# PCB2.net
KiCad netlist of a schematic drawn in Altium Designer
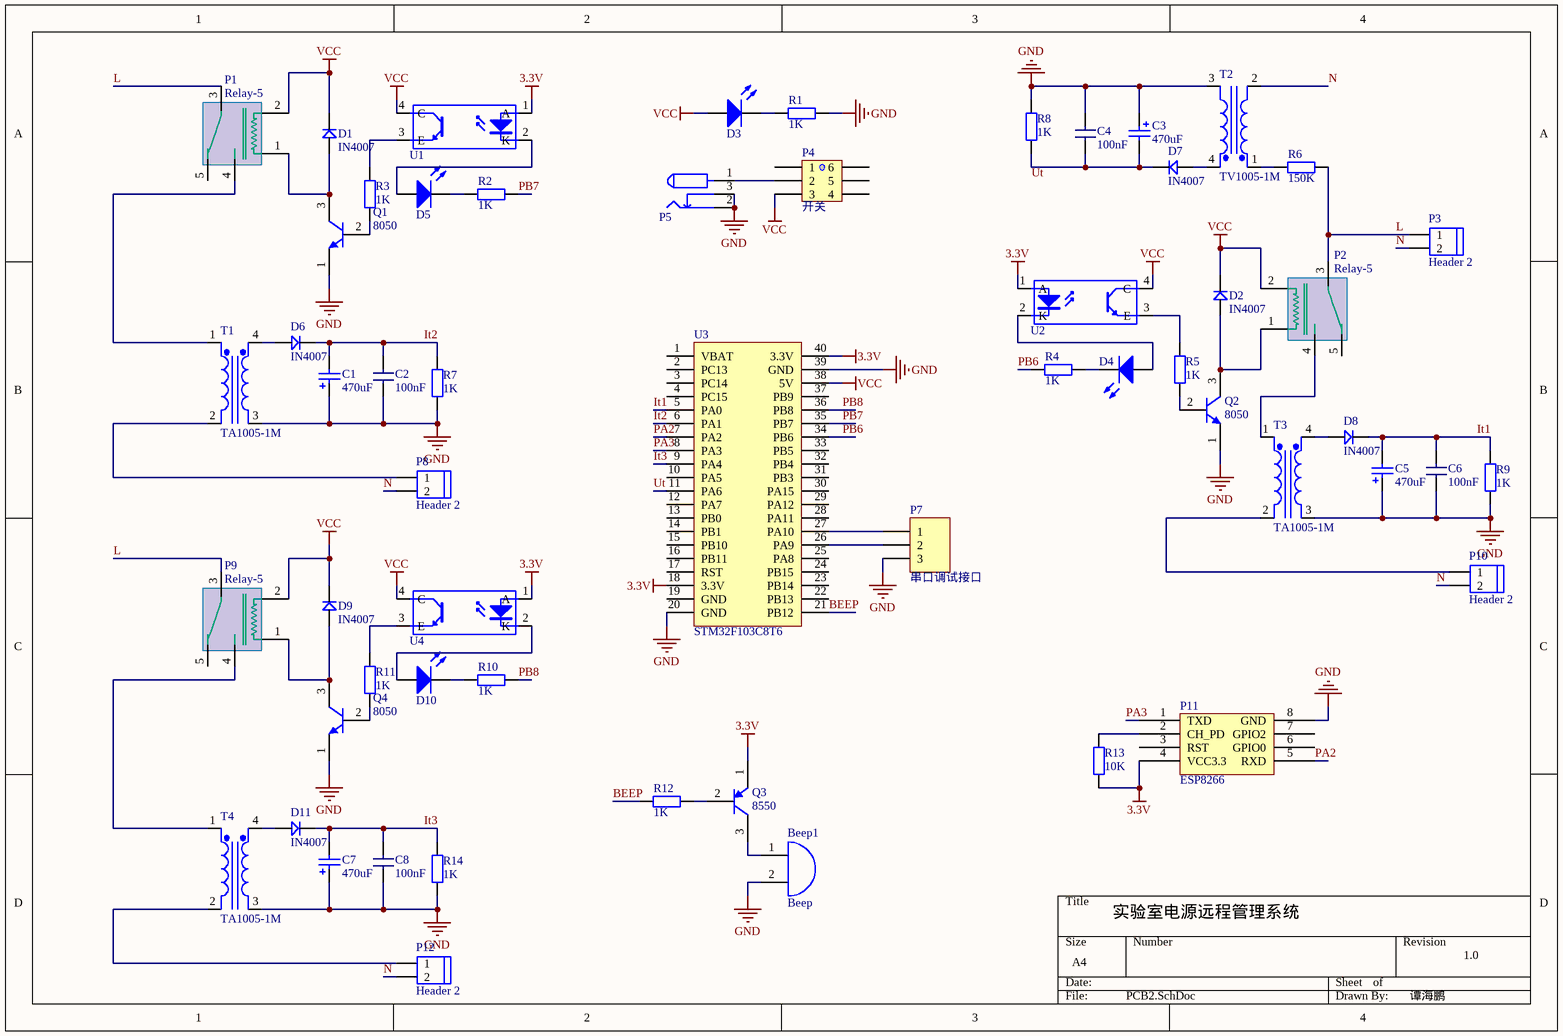
[diagram p0: PCB2.SchDoc]

(export (version "E")
  (design (tool "Eeschema 10.0.6"))
  (components
    (comp (ref "Beep1")
      (value "Beep")
      (footprint "Bell")
      (description "蜂鸣器")
      (libsource (lib "PCB2") (part "Bell"))
    )
    (comp (ref "C1")
      (value "470uF")
      (footprint "Cap")
      (description "电解电容")
      (fields (field (name "Comment") "CAP-A"))
      (libsource (lib "PCB2") (part "CAP-A"))
    )
    (comp (ref "C2")
      (value "100nF")
      (footprint "Cap")
      (description "瓷片电容")
      (fields (field (name "Comment") "CAP-B"))
      (libsource (lib "PCB2") (part "CAP-B"))
    )
    (comp (ref "C3")
      (value "470uF")
      (footprint "Cap")
      (description "电解电容")
      (fields (field (name "Comment") "CAP-A"))
      (libsource (lib "PCB2") (part "CAP-A"))
    )
    (comp (ref "C4")
      (value "100nF")
      (footprint "Cap")
      (description "瓷片电容")
      (fields (field (name "Comment") "CAP-B"))
      (libsource (lib "PCB2") (part "CAP-B"))
    )
    (comp (ref "C5")
      (value "470uF")
      (footprint "Cap")
      (description "电解电容")
      (fields (field (name "Comment") "CAP-A"))
      (libsource (lib "PCB2") (part "CAP-A"))
    )
    (comp (ref "C6")
      (value "100nF")
      (footprint "Cap")
      (description "瓷片电容")
      (fields (field (name "Comment") "CAP-B"))
      (libsource (lib "PCB2") (part "CAP-B"))
    )
    (comp (ref "C7")
      (value "470uF")
      (footprint "Cap")
      (description "电解电容")
      (fields (field (name "Comment") "CAP-A"))
      (libsource (lib "PCB2") (part "CAP-A"))
    )
    (comp (ref "C8")
      (value "100nF")
      (footprint "Cap")
      (description "瓷片电容")
      (fields (field (name "Comment") "CAP-B"))
      (libsource (lib "PCB2") (part "CAP-B"))
    )
    (comp (ref "D1")
      (value "IN4007")
      (footprint "Diode")
      (description "整流二极管")
      (fields (field (name "Comment") "Diode"))
      (libsource (lib "PCB2") (part "Diode"))
    )
    (comp (ref "D2")
      (value "IN4007")
      (footprint "Diode")
      (description "整流二极管")
      (fields (field (name "Comment") "Diode"))
      (libsource (lib "PCB2") (part "Diode"))
    )
    (comp (ref "D3") (value "LED") (footprint "LED") (libsource (lib "Component") (part "LED")))
    (comp (ref "D4") (value "LED") (footprint "LED") (libsource (lib "Component") (part "LED")))
    (comp (ref "D5") (value "LED") (footprint "LED") (libsource (lib "Component") (part "LED")))
    (comp (ref "D6")
      (value "IN4007")
      (footprint "Diode")
      (description "整流二极管")
      (fields (field (name "Comment") "Diode"))
      (libsource (lib "PCB2") (part "Diode"))
    )
    (comp (ref "D7")
      (value "IN4007")
      (footprint "Diode")
      (description "整流二极管")
      (fields (field (name "Comment") "Diode"))
      (libsource (lib "PCB2") (part "Diode"))
    )
    (comp (ref "D8")
      (value "IN4007")
      (footprint "Diode")
      (description "整流二极管")
      (fields (field (name "Comment") "Diode"))
      (libsource (lib "PCB2") (part "Diode"))
    )
    (comp (ref "D9")
      (value "IN4007")
      (footprint "Diode")
      (description "整流二极管")
      (fields (field (name "Comment") "Diode"))
      (libsource (lib "PCB2") (part "Diode"))
    )
    (comp (ref "D10") (value "LED") (footprint "LED") (libsource (lib "Component") (part "LED")))
    (comp (ref "D11")
      (value "IN4007")
      (footprint "Diode")
      (description "整流二极管")
      (fields (field (name "Comment") "Diode"))
      (libsource (lib "PCB2") (part "Diode"))
    )
    (comp (ref "P1")
      (value "Relay-5")
      (footprint "Relay")
      (description "5针继电器")
      (libsource (lib "") (part "Relay-5_1"))
    )
    (comp (ref "P2")
      (value "Relay-5")
      (footprint "Relay")
      (description "5针继电器")
      (libsource (lib "原理图库") (part "Relay-5"))
    )
    (comp (ref "P3")
      (value "Header 2")
      (footprint "HDR1X2")
      (description "两孔端子")
      (libsource (lib "原理图库") (part "Header 2"))
    )
    (comp (ref "P4") (value "开关") (footprint "Switch") (libsource (lib "PCB2") (part "Switch")))
    (comp (ref "P5")
      (value "电源插座")
      (footprint "DC")
      (description "DC电源插口")
      (libsource (lib "PCB2") (part "POWER"))
    )
    (comp (ref "P7")
      (value "串口调试接口")
      (footprint "HDR1X3")
      (description "Header, 3-Pin")
      (fields (field (name "PUBLISHER") "Altium Limited"))
      (libsource (lib "Miscellaneous Connectors") (part "Header 3"))
    )
    (comp (ref "P8")
      (value "Header 2")
      (footprint "HDR1X2")
      (description "两孔端子")
      (libsource (lib "原理图库") (part "Header 2"))
    )
    (comp (ref "P9")
      (value "Relay-5")
      (footprint "Relay")
      (description "5针继电器")
      (libsource (lib "") (part "Relay-5_1"))
    )
    (comp (ref "P10")
      (value "Header 2")
      (footprint "HDR1X2")
      (description "两孔端子")
      (libsource (lib "原理图库") (part "Header 2"))
    )
    (comp (ref "P11")
      (value "ESP8266")
      (footprint "ESP8266")
      (description "WIFI模块（8针）")
      (libsource (lib "PCB2") (part "ESP8266"))
    )
    (comp (ref "P12")
      (value "Header 2")
      (footprint "HDR1X2")
      (description "两孔端子")
      (libsource (lib "原理图库") (part "Header 2"))
    )
    (comp (ref "Q1")
      (value "8050")
      (footprint "Triode")
      (description "NPN")
      (libsource (lib "原理图库") (part "NPN"))
    )
    (comp (ref "Q2")
      (value "8050")
      (footprint "Triode")
      (description "NPN")
      (libsource (lib "原理图库") (part "NPN"))
    )
    (comp (ref "Q3")
      (value "8550")
      (footprint "Triode")
      (description "PNP")
      (libsource (lib "原理图库") (part "PNP"))
    )
    (comp (ref "Q4")
      (value "8050")
      (footprint "Triode")
      (description "NPN")
      (libsource (lib "原理图库") (part "NPN"))
    )
    (comp (ref "R1")
      (value "1K")
      (footprint "RES")
      (description "电阻")
      (fields (field (name "Comment") "RES"))
      (libsource (lib "") (part "RES_1"))
    )
    (comp (ref "R2")
      (value "1K")
      (footprint "RES")
      (description "电阻")
      (fields (field (name "Comment") "RES"))
      (libsource (lib "") (part "RES_1"))
    )
    (comp (ref "R3")
      (value "1K")
      (footprint "RES")
      (description "电阻")
      (fields (field (name "Comment") "RES"))
      (libsource (lib "PCB2") (part "RES"))
    )
    (comp (ref "R4")
      (value "1K")
      (footprint "RES")
      (description "电阻")
      (fields (field (name "Comment") "RES"))
      (libsource (lib "") (part "RES_1"))
    )
    (comp (ref "R5")
      (value "1K")
      (footprint "RES")
      (description "电阻")
      (fields (field (name "Comment") "RES"))
      (libsource (lib "") (part "RES_2"))
    )
    (comp (ref "R6")
      (value "150K")
      (footprint "RES")
      (description "电阻")
      (fields (field (name "Comment") "RES"))
      (libsource (lib "") (part "RES_1"))
    )
    (comp (ref "R7")
      (value "1K")
      (footprint "RES")
      (description "电阻")
      (fields (field (name "Comment") "RES"))
      (libsource (lib "PCB2") (part "RES"))
    )
    (comp (ref "R8")
      (value "1K")
      (footprint "RES")
      (description "电阻")
      (fields (field (name "Comment") "RES"))
      (libsource (lib "") (part "RES_2"))
    )
    (comp (ref "R9")
      (value "1K")
      (footprint "RES")
      (description "电阻")
      (fields (field (name "Comment") "RES"))
      (libsource (lib "PCB2") (part "RES"))
    )
    (comp (ref "R10")
      (value "1K")
      (footprint "RES")
      (description "电阻")
      (fields (field (name "Comment") "RES"))
      (libsource (lib "") (part "RES_3"))
    )
    (comp (ref "R11")
      (value "1K")
      (footprint "RES")
      (description "电阻")
      (fields (field (name "Comment") "RES"))
      (libsource (lib "PCB2") (part "RES"))
    )
    (comp (ref "R12")
      (value "1K")
      (footprint "RES")
      (description "电阻")
      (fields (field (name "Comment") "RES"))
      (libsource (lib "") (part "RES_3"))
    )
    (comp (ref "R13")
      (value "10K")
      (footprint "RES")
      (description "电阻")
      (fields (field (name "Comment") "RES"))
      (libsource (lib "PCB2") (part "RES"))
    )
    (comp (ref "R14")
      (value "1K")
      (footprint "RES")
      (description "电阻")
      (fields (field (name "Comment") "RES"))
      (libsource (lib "PCB2") (part "RES"))
    )
    (comp (ref "T1")
      (value "TA1005-1M")
      (footprint "Transforme")
      (description "电流互感器")
      (libsource (lib "PCB2") (part "Transforme-A"))
    )
    (comp (ref "T2")
      (value "TV1005-1M")
      (footprint "Transforme")
      (description "电压互感器")
      (libsource (lib "PCB2") (part "Transforme-V"))
    )
    (comp (ref "T3")
      (value "TA1005-1M")
      (footprint "Transforme")
      (description "电流互感器")
      (libsource (lib "PCB2") (part "Transforme-A"))
    )
    (comp (ref "T4")
      (value "TA1005-1M")
      (footprint "Transforme")
      (description "电流互感器")
      (libsource (lib "PCB2") (part "Transforme-A"))
    )
    (comp (ref "U1")
      (value "Optoisolator")
      (footprint "DIP-4")
      (description "光耦隔离器")
      (libsource (lib "PCB2") (part "Optoisolator"))
    )
    (comp (ref "U2")
      (value "Optoisolator")
      (footprint "DIP-4")
      (description "光耦隔离器")
      (libsource (lib "PCB2") (part "Optoisolator"))
    )
    (comp (ref "U3")
      (value "STM32F103C8T6")
      (footprint "STM32F103C8T6")
      (description "STM32最小系统（40针）")
      (libsource (lib "PCB2") (part "STM32F103C8T6"))
    )
    (comp (ref "U4")
      (value "Optoisolator")
      (footprint "DIP-4")
      (description "光耦隔离器")
      (libsource (lib "PCB2") (part "Optoisolator"))
    )
  )
  (nets
    (net (code "1") (name "/BEEP") (class "Default")
      (node (ref "R12") (pin "1") (pinfunction "1_1") (pintype "passive"))
      (node (ref "U3") (pin "21") (pinfunction "PB12_21") (pintype "passive"))
    )
    (net (code "2") (name "/It1") (class "Default")
      (node (ref "C5") (pin "2") (pinfunction "2_2") (pintype "passive"))
      (node (ref "C6") (pin "2") (pintype "passive"))
      (node (ref "D8") (pin "2") (pintype "passive"))
      (node (ref "R9") (pin "2") (pinfunction "2_2") (pintype "passive"))
      (node (ref "U3") (pin "5") (pinfunction "PA0_5") (pintype "passive"))
    )
    (net (code "3") (name "/It2") (class "Default")
      (node (ref "C1") (pin "2") (pinfunction "2_2") (pintype "passive"))
      (node (ref "C2") (pin "2") (pintype "passive"))
      (node (ref "D6") (pin "2") (pintype "passive"))
      (node (ref "R7") (pin "2") (pinfunction "2_2") (pintype "passive"))
      (node (ref "U3") (pin "6") (pinfunction "PA1_6") (pintype "passive"))
    )
    (net (code "4") (name "/It3") (class "Default")
      (node (ref "C7") (pin "2") (pinfunction "2_2") (pintype "passive"))
      (node (ref "C8") (pin "2") (pintype "passive"))
      (node (ref "D11") (pin "2") (pintype "passive"))
      (node (ref "R14") (pin "2") (pinfunction "2_2") (pintype "passive"))
      (node (ref "U3") (pin "9") (pinfunction "PA4_9") (pintype "passive"))
    )
    (net (code "5") (name "/L") (class "Default")
      (node (ref "P1") (pin "3") (pinfunction "3_3") (pintype "passive"))
      (node (ref "P2") (pin "3") (pinfunction "3_3") (pintype "passive"))
      (node (ref "P3") (pin "1") (pinfunction "1_1") (pintype "passive"))
      (node (ref "P9") (pin "3") (pinfunction "3_3") (pintype "passive"))
      (node (ref "R6") (pin "1") (pinfunction "1_1") (pintype "passive"))
    )
    (net (code "6") (name "/N") (class "Default")
      (node (ref "P10") (pin "2") (pinfunction "2_2") (pintype "passive"))
      (node (ref "P12") (pin "2") (pinfunction "2_2") (pintype "passive"))
      (node (ref "P3") (pin "2") (pinfunction "2_2") (pintype "passive"))
      (node (ref "P8") (pin "2") (pinfunction "2_2") (pintype "passive"))
      (node (ref "T2") (pin "2") (pinfunction "Pri-_2") (pintype "passive"))
    )
    (net (code "7") (name "/PA2") (class "Default")
      (node (ref "P11") (pin "5") (pinfunction "RXD_5") (pintype "passive"))
      (node (ref "U3") (pin "7") (pinfunction "PA2_7") (pintype "passive"))
    )
    (net (code "8") (name "/PA3") (class "Default")
      (node (ref "P11") (pin "1") (pinfunction "TXD_1") (pintype "passive"))
      (node (ref "U3") (pin "8") (pinfunction "PA3_8") (pintype "passive"))
    )
    (net (code "9") (name "/PB6") (class "Default")
      (node (ref "R4") (pin "2") (pinfunction "2_2") (pintype "passive"))
      (node (ref "U3") (pin "34") (pinfunction "PB6_34") (pintype "passive"))
    )
    (net (code "10") (name "/PB7") (class "Default")
      (node (ref "R2") (pin "1") (pinfunction "1_1") (pintype "passive"))
      (node (ref "U3") (pin "35") (pinfunction "PB7_35") (pintype "passive"))
    )
    (net (code "11") (name "/PB8") (class "Default")
      (node (ref "R10") (pin "2") (pinfunction "2_2") (pintype "passive"))
      (node (ref "U3") (pin "36") (pinfunction "PB8_36") (pintype "passive"))
    )
    (net (code "12") (name "/Ut") (class "Default")
      (node (ref "U3") (pin "11") (pinfunction "PA6_11") (pintype "passive"))
    )
    (net (code "13") (name "3.3V") (class "Default")
      (node (ref "P11") (pin "4") (pinfunction "VCC3.3_4") (pintype "passive"))
      (node (ref "Q3") (pin "1") (pinfunction "E_1") (pintype "passive"))
      (node (ref "R13") (pin "1") (pinfunction "1_1") (pintype "passive"))
      (node (ref "U1") (pin "1") (pinfunction "A_1") (pintype "passive"))
      (node (ref "U2") (pin "1") (pinfunction "A_1") (pintype "passive"))
      (node (ref "U3") (pin "18") (pinfunction "3.3V_18") (pintype "passive"))
      (node (ref "U3") (pin "40") (pinfunction "3.3V_40") (pintype "passive"))
      (node (ref "U4") (pin "1") (pinfunction "A_1") (pintype "passive"))
    )
    (net (code "14") (name "GND") (class "Default")
      (node (ref "Beep1") (pin "2") (pinfunction "B_2") (pintype "passive"))
      (node (ref "C1") (pin "1") (pinfunction "1_1") (pintype "passive"))
      (node (ref "C2") (pin "1") (pintype "passive"))
      (node (ref "C3") (pin "1") (pinfunction "1_1") (pintype "passive"))
      (node (ref "C4") (pin "1") (pintype "passive"))
      (node (ref "C5") (pin "1") (pinfunction "1_1") (pintype "passive"))
      (node (ref "C6") (pin "1") (pintype "passive"))
      (node (ref "C7") (pin "1") (pinfunction "1_1") (pintype "passive"))
      (node (ref "C8") (pin "1") (pintype "passive"))
      (node (ref "P11") (pin "8") (pinfunction "GND_8") (pintype "passive"))
      (node (ref "P5") (pin "2") (pintype "passive"))
      (node (ref "P5") (pin "3") (pintype "passive"))
      (node (ref "P7") (pin "3") (pinfunction "3_3") (pintype "passive"))
      (node (ref "Q1") (pin "1") (pinfunction "2_1") (pintype "passive"))
      (node (ref "Q2") (pin "1") (pinfunction "2_1") (pintype "passive"))
      (node (ref "Q4") (pin "1") (pinfunction "2_1") (pintype "passive"))
      (node (ref "R1") (pin "1") (pinfunction "1_1") (pintype "passive"))
      (node (ref "R14") (pin "1") (pinfunction "1_1") (pintype "passive"))
      (node (ref "R7") (pin "1") (pinfunction "1_1") (pintype "passive"))
      (node (ref "R8") (pin "1") (pinfunction "1_1") (pintype "passive"))
      (node (ref "R9") (pin "1") (pinfunction "1_1") (pintype "passive"))
      (node (ref "T1") (pin "3") (pinfunction "Sec-_3") (pintype "passive"))
      (node (ref "T2") (pin "3") (pinfunction "Sec-_3") (pintype "passive"))
      (node (ref "T3") (pin "3") (pinfunction "Sec-_3") (pintype "passive"))
      (node (ref "T4") (pin "3") (pinfunction "Sec-_3") (pintype "passive"))
      (node (ref "U3") (pin "20") (pinfunction "GND_20") (pintype "passive"))
      (node (ref "U3") (pin "39") (pinfunction "GND_39") (pintype "passive"))
    )
    (net (code "15") (name "Net-(Beep1-A)") (class "Default")
      (node (ref "Beep1") (pin "1") (pinfunction "A_1") (pintype "passive"))
      (node (ref "Q3") (pin "3") (pinfunction "C_3") (pintype "passive"))
    )
    (net (code "16") (name "Net-(C3-Pad2)") (class "Default")
      (node (ref "C3") (pin "2") (pinfunction "2_2") (pintype "passive"))
      (node (ref "C4") (pin "2") (pintype "passive"))
      (node (ref "D7") (pin "2") (pintype "passive"))
      (node (ref "R8") (pin "2") (pinfunction "2_2") (pintype "passive"))
    )
    (net (code "17") (name "Net-(D3-K)") (class "Default")
      (node (ref "D3") (pin "2") (pinfunction "K_2") (pintype "passive"))
      (node (ref "R1") (pin "2") (pinfunction "2_2") (pintype "passive"))
    )
    (net (code "18") (name "Net-(D4-A)") (class "Default")
      (node (ref "D4") (pin "1") (pinfunction "A_1") (pintype "passive"))
      (node (ref "U2") (pin "2") (pinfunction "K_2") (pintype "passive"))
    )
    (net (code "19") (name "Net-(D4-K)") (class "Default")
      (node (ref "D4") (pin "2") (pinfunction "K_2") (pintype "passive"))
      (node (ref "R4") (pin "1") (pinfunction "1_1") (pintype "passive"))
    )
    (net (code "20") (name "Net-(D5-A)") (class "Default")
      (node (ref "D5") (pin "1") (pinfunction "A_1") (pintype "passive"))
      (node (ref "U1") (pin "2") (pinfunction "K_2") (pintype "passive"))
    )
    (net (code "21") (name "Net-(D5-K)") (class "Default")
      (node (ref "D5") (pin "2") (pinfunction "K_2") (pintype "passive"))
      (node (ref "R2") (pin "2") (pinfunction "2_2") (pintype "passive"))
    )
    (net (code "22") (name "Net-(D10-A)") (class "Default")
      (node (ref "D10") (pin "1") (pinfunction "A_1") (pintype "passive"))
      (node (ref "U4") (pin "2") (pinfunction "K_2") (pintype "passive"))
    )
    (net (code "23") (name "Net-(D10-K)") (class "Default")
      (node (ref "D10") (pin "2") (pinfunction "K_2") (pintype "passive"))
      (node (ref "R10") (pin "1") (pinfunction "1_1") (pintype "passive"))
    )
    (net (code "24") (name "Net-(P4-Pad2)") (class "Default")
      (node (ref "P4") (pin "2") (pinfunction "2_2") (pintype "passive"))
      (node (ref "P5") (pin "1") (pintype "passive"))
    )
    (net (code "25") (name "Net-(P11-CH_PD)") (class "Default")
      (node (ref "P11") (pin "2") (pinfunction "CH_PD_2") (pintype "passive"))
      (node (ref "R13") (pin "2") (pinfunction "2_2") (pintype "passive"))
    )
    (net (code "26") (name "Net-(Q1-B)") (class "Default")
      (node (ref "Q1") (pin "2") (pinfunction "B_2") (pintype "passive"))
      (node (ref "R3") (pin "1") (pinfunction "1_1") (pintype "passive"))
    )
    (net (code "27") (name "Net-(Q1-C)") (class "Default")
      (node (ref "D1") (pin "1") (pintype "passive"))
      (node (ref "P1") (pin "1") (pinfunction "1_1") (pintype "passive"))
      (node (ref "Q1") (pin "3") (pinfunction "C_3") (pintype "passive"))
    )
    (net (code "28") (name "Net-(Q2-B)") (class "Default")
      (node (ref "Q2") (pin "2") (pinfunction "B_2") (pintype "passive"))
      (node (ref "R5") (pin "2") (pinfunction "2_2") (pintype "passive"))
    )
    (net (code "29") (name "Net-(Q2-C)") (class "Default")
      (node (ref "D2") (pin "1") (pintype "passive"))
      (node (ref "P2") (pin "1") (pinfunction "1_1") (pintype "passive"))
      (node (ref "Q2") (pin "3") (pinfunction "C_3") (pintype "passive"))
    )
    (net (code "30") (name "Net-(Q3-B)") (class "Default")
      (node (ref "Q3") (pin "2") (pinfunction "B_2") (pintype "passive"))
      (node (ref "R12") (pin "2") (pinfunction "2_2") (pintype "passive"))
    )
    (net (code "31") (name "Net-(Q4-B)") (class "Default")
      (node (ref "Q4") (pin "2") (pinfunction "B_2") (pintype "passive"))
      (node (ref "R11") (pin "1") (pinfunction "1_1") (pintype "passive"))
    )
    (net (code "32") (name "Net-(Q4-C)") (class "Default")
      (node (ref "D9") (pin "1") (pintype "passive"))
      (node (ref "P9") (pin "1") (pinfunction "1_1") (pintype "passive"))
      (node (ref "Q4") (pin "3") (pinfunction "C_3") (pintype "passive"))
    )
    (net (code "33") (name "Net-(T1-Pri+)") (class "Default")
      (node (ref "P1") (pin "4") (pinfunction "4_4") (pintype "passive"))
      (node (ref "T1") (pin "1") (pinfunction "Pri+_1") (pintype "passive"))
    )
    (net (code "34") (name "Net-(T1-Pri-)") (class "Default")
      (node (ref "P8") (pin "1") (pinfunction "1_1") (pintype "passive"))
      (node (ref "T1") (pin "2") (pinfunction "Pri-_2") (pintype "passive"))
    )
    (net (code "35") (name "Net-(T1-Sec+)") (class "Default")
      (node (ref "D6") (pin "1") (pintype "passive"))
      (node (ref "T1") (pin "4") (pinfunction "Sec+_4") (pintype "passive"))
    )
    (net (code "36") (name "Net-(T2-Pri+)") (class "Default")
      (node (ref "R6") (pin "2") (pinfunction "2_2") (pintype "passive"))
      (node (ref "T2") (pin "1") (pinfunction "Pri+_1") (pintype "passive"))
    )
    (net (code "37") (name "Net-(T2-Sec+)") (class "Default")
      (node (ref "D7") (pin "1") (pintype "passive"))
      (node (ref "T2") (pin "4") (pinfunction "Sec+_4") (pintype "passive"))
    )
    (net (code "38") (name "Net-(T3-Pri+)") (class "Default")
      (node (ref "P2") (pin "4") (pinfunction "4_4") (pintype "passive"))
      (node (ref "T3") (pin "1") (pinfunction "Pri+_1") (pintype "passive"))
    )
    (net (code "39") (name "Net-(T3-Pri-)") (class "Default")
      (node (ref "P10") (pin "1") (pinfunction "1_1") (pintype "passive"))
      (node (ref "T3") (pin "2") (pinfunction "Pri-_2") (pintype "passive"))
    )
    (net (code "40") (name "Net-(T3-Sec+)") (class "Default")
      (node (ref "D8") (pin "1") (pintype "passive"))
      (node (ref "T3") (pin "4") (pinfunction "Sec+_4") (pintype "passive"))
    )
    (net (code "41") (name "Net-(T4-Pri+)") (class "Default")
      (node (ref "P9") (pin "4") (pinfunction "4_4") (pintype "passive"))
      (node (ref "T4") (pin "1") (pinfunction "Pri+_1") (pintype "passive"))
    )
    (net (code "42") (name "Net-(T4-Pri-)") (class "Default")
      (node (ref "P12") (pin "1") (pinfunction "1_1") (pintype "passive"))
      (node (ref "T4") (pin "2") (pinfunction "Pri-_2") (pintype "passive"))
    )
    (net (code "43") (name "Net-(T4-Sec+)") (class "Default")
      (node (ref "D11") (pin "1") (pintype "passive"))
      (node (ref "T4") (pin "4") (pinfunction "Sec+_4") (pintype "passive"))
    )
    (net (code "44") (name "Net-(U1-E)") (class "Default")
      (node (ref "R3") (pin "2") (pinfunction "2_2") (pintype "passive"))
      (node (ref "U1") (pin "3") (pinfunction "E_3") (pintype "passive"))
    )
    (net (code "45") (name "Net-(U2-E)") (class "Default")
      (node (ref "R5") (pin "1") (pinfunction "1_1") (pintype "passive"))
      (node (ref "U2") (pin "3") (pinfunction "E_3") (pintype "passive"))
    )
    (net (code "46") (name "Net-(U3-PA9)") (class "Default")
      (node (ref "P7") (pin "2") (pinfunction "2_2") (pintype "passive"))
      (node (ref "U3") (pin "26") (pinfunction "PA9_26") (pintype "passive"))
    )
    (net (code "47") (name "Net-(U3-PA10)") (class "Default")
      (node (ref "P7") (pin "1") (pinfunction "1_1") (pintype "passive"))
      (node (ref "U3") (pin "27") (pinfunction "PA10_27") (pintype "passive"))
    )
    (net (code "48") (name "Net-(U4-E)") (class "Default")
      (node (ref "R11") (pin "2") (pinfunction "2_2") (pintype "passive"))
      (node (ref "U4") (pin "3") (pinfunction "E_3") (pintype "passive"))
    )
    (net (code "49") (name "VCC") (class "Default")
      (node (ref "D1") (pin "2") (pintype "passive"))
      (node (ref "D2") (pin "2") (pintype "passive"))
      (node (ref "D3") (pin "1") (pinfunction "A_1") (pintype "passive"))
      (node (ref "D9") (pin "2") (pintype "passive"))
      (node (ref "P1") (pin "2") (pinfunction "2_2") (pintype "passive"))
      (node (ref "P2") (pin "2") (pinfunction "2_2") (pintype "passive"))
      (node (ref "P4") (pin "3") (pinfunction "3_3") (pintype "passive"))
      (node (ref "P9") (pin "2") (pinfunction "2_2") (pintype "passive"))
      (node (ref "U1") (pin "4") (pinfunction "C_4") (pintype "passive"))
      (node (ref "U2") (pin "4") (pinfunction "C_4") (pintype "passive"))
      (node (ref "U3") (pin "38") (pinfunction "5V_38") (pintype "passive"))
      (node (ref "U4") (pin "4") (pinfunction "C_4") (pintype "passive"))
    )
    (net (code "50") (name "unconnected-(P1-Pad5)") (class "Default")
      (node (ref "P1") (pin "5") (pinfunction "5_5") (pintype "passive"))
    )
    (net (code "51") (name "unconnected-(P2-Pad5)") (class "Default")
      (node (ref "P2") (pin "5") (pinfunction "5_5") (pintype "passive"))
    )
    (net (code "52") (name "unconnected-(P4-Pad1)") (class "Default")
      (node (ref "P4") (pin "1") (pinfunction "1_1") (pintype "passive"))
    )
    (net (code "53") (name "unconnected-(P4-Pad4)") (class "Default")
      (node (ref "P4") (pin "4") (pinfunction "4_4") (pintype "passive"))
    )
    (net (code "54") (name "unconnected-(P4-Pad5)") (class "Default")
      (node (ref "P4") (pin "5") (pinfunction "5_5") (pintype "passive"))
    )
    (net (code "55") (name "unconnected-(P4-Pad6)") (class "Default")
      (node (ref "P4") (pin "6") (pinfunction "6_6") (pintype "passive"))
    )
    (net (code "56") (name "unconnected-(P9-Pad5)") (class "Default")
      (node (ref "P9") (pin "5") (pinfunction "5_5") (pintype "passive"))
    )
    (net (code "57") (name "unconnected-(P11-GPIO0-Pad6)") (class "Default")
      (node (ref "P11") (pin "6") (pinfunction "GPIO0_6") (pintype "passive"))
    )
    (net (code "58") (name "unconnected-(P11-GPIO2-Pad7)") (class "Default")
      (node (ref "P11") (pin "7") (pinfunction "GPIO2_7") (pintype "passive"))
    )
    (net (code "59") (name "unconnected-(P11-RST-Pad3)") (class "Default")
      (node (ref "P11") (pin "3") (pinfunction "RST_3") (pintype "passive"))
    )
    (net (code "60") (name "unconnected-(U3-GND-Pad19)") (class "Default")
      (node (ref "U3") (pin "19") (pinfunction "GND_19") (pintype "passive"))
    )
    (net (code "61") (name "unconnected-(U3-PA5-Pad10)") (class "Default")
      (node (ref "U3") (pin "10") (pinfunction "PA5_10") (pintype "passive"))
    )
    (net (code "62") (name "unconnected-(U3-PA7-Pad12)") (class "Default")
      (node (ref "U3") (pin "12") (pinfunction "PA7_12") (pintype "passive"))
    )
    (net (code "63") (name "unconnected-(U3-PA8-Pad25)") (class "Default")
      (node (ref "U3") (pin "25") (pinfunction "PA8_25") (pintype "passive"))
    )
    (net (code "64") (name "unconnected-(U3-PA11-Pad28)") (class "Default")
      (node (ref "U3") (pin "28") (pinfunction "PA11_28") (pintype "passive"))
    )
    (net (code "65") (name "unconnected-(U3-PA12-Pad29)") (class "Default")
      (node (ref "U3") (pin "29") (pinfunction "PA12_29") (pintype "passive"))
    )
    (net (code "66") (name "unconnected-(U3-PA15-Pad30)") (class "Default")
      (node (ref "U3") (pin "30") (pinfunction "PA15_30") (pintype "passive"))
    )
    (net (code "67") (name "unconnected-(U3-PB0-Pad13)") (class "Default")
      (node (ref "U3") (pin "13") (pinfunction "PB0_13") (pintype "passive"))
    )
    (net (code "68") (name "unconnected-(U3-PB1-Pad14)") (class "Default")
      (node (ref "U3") (pin "14") (pinfunction "PB1_14") (pintype "passive"))
    )
    (net (code "69") (name "unconnected-(U3-PB3-Pad31)") (class "Default")
      (node (ref "U3") (pin "31") (pinfunction "PB3_31") (pintype "passive"))
    )
    (net (code "70") (name "unconnected-(U3-PB4-Pad32)") (class "Default")
      (node (ref "U3") (pin "32") (pinfunction "PB4_32") (pintype "passive"))
    )
    (net (code "71") (name "unconnected-(U3-PB5-Pad33)") (class "Default")
      (node (ref "U3") (pin "33") (pinfunction "PB5_33") (pintype "passive"))
    )
    (net (code "72") (name "unconnected-(U3-PB9-Pad37)") (class "Default")
      (node (ref "U3") (pin "37") (pinfunction "PB9_37") (pintype "passive"))
    )
    (net (code "73") (name "unconnected-(U3-PB10-Pad15)") (class "Default")
      (node (ref "U3") (pin "15") (pinfunction "PB10_15") (pintype "passive"))
    )
    (net (code "74") (name "unconnected-(U3-PB11-Pad16)") (class "Default")
      (node (ref "U3") (pin "16") (pinfunction "PB11_16") (pintype "passive"))
    )
    (net (code "75") (name "unconnected-(U3-PB13-Pad22)") (class "Default")
      (node (ref "U3") (pin "22") (pinfunction "PB13_22") (pintype "passive"))
    )
    (net (code "76") (name "unconnected-(U3-PB14-Pad23)") (class "Default")
      (node (ref "U3") (pin "23") (pinfunction "PB14_23") (pintype "passive"))
    )
    (net (code "77") (name "unconnected-(U3-PB15-Pad24)") (class "Default")
      (node (ref "U3") (pin "24") (pinfunction "PB15_24") (pintype "passive"))
    )
    (net (code "78") (name "unconnected-(U3-PC13-Pad2)") (class "Default")
      (node (ref "U3") (pin "2") (pinfunction "PC13_2") (pintype "passive"))
    )
    (net (code "79") (name "unconnected-(U3-PC14-Pad3)") (class "Default")
      (node (ref "U3") (pin "3") (pinfunction "PC14_3") (pintype "passive"))
    )
    (net (code "80") (name "unconnected-(U3-PC15-Pad4)") (class "Default")
      (node (ref "U3") (pin "4") (pinfunction "PC15_4") (pintype "passive"))
    )
    (net (code "81") (name "unconnected-(U3-RST-Pad17)") (class "Default")
      (node (ref "U3") (pin "17") (pinfunction "RST_17") (pintype "passive"))
    )
    (net (code "82") (name "unconnected-(U3-VBAT-Pad1)") (class "Default")
      (node (ref "U3") (pin "1") (pinfunction "VBAT_1") (pintype "passive"))
    )
  )
)
